# Conectores.net
KiCad netlist of a schematic drawn in Altium Designer
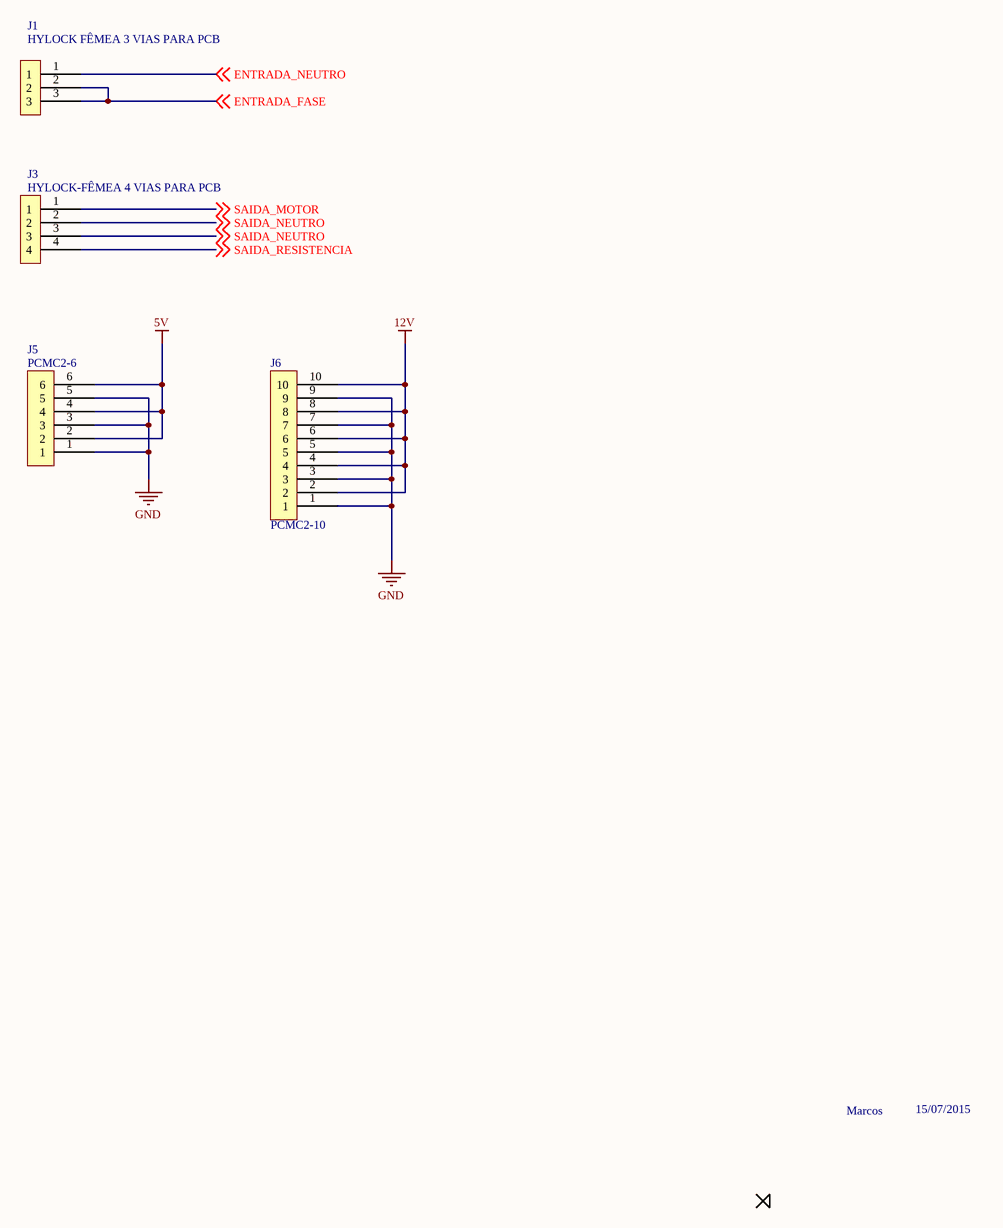
[diagram p0: Conectores.SchDoc]

(export (version "E")
  (design (tool "Eeschema 10.0.6"))
  (components
    (comp (ref "J1")
      (value "HYLOCK FÊMEA 3 VIAS PARA PCB")
      (footprint "CONECTOR HYLOCK 3 VIAS")
      (description "PCMC2-3")
      (libsource (lib "AquinoLib") (part "PCMC2-3"))
    )
    (comp (ref "J3")
      (value "HYLOCK-FÊMEA 4 VIAS PARA PCB")
      (footprint "CONECTOR HYLOK 4 VIAS")
      (description "PCMC2-4")
      (libsource (lib "AquinoLib") (part "PCMC2-4"))
    )
    (comp (ref "J5") (value "PCMC2-6") (footprint "PCMC2-6") (libsource (lib "AquinoLib") (part "PCMC2-6")))
    (comp (ref "J6")
      (value "PCMC2-10")
      (footprint "PCMC2-10")
      (libsource (lib "AquinoLib") (part "PCMC2-10"))
    )
  )
  (nets
    (net (code "1") (name "5V") (class "Default")
      (node (ref "J5") (pin "2") (pinfunction "2_2") (pintype "passive"))
      (node (ref "J5") (pin "4") (pinfunction "4_4") (pintype "passive"))
      (node (ref "J5") (pin "6") (pinfunction "6_6") (pintype "passive"))
    )
    (net (code "2") (name "12V") (class "Default")
      (node (ref "J6") (pin "10") (pinfunction "10_10") (pintype "passive"))
      (node (ref "J6") (pin "2") (pinfunction "2_2") (pintype "passive"))
      (node (ref "J6") (pin "4") (pinfunction "4_4") (pintype "passive"))
      (node (ref "J6") (pin "6") (pinfunction "6_6") (pintype "passive"))
      (node (ref "J6") (pin "8") (pinfunction "8_8") (pintype "passive"))
    )
    (net (code "3") (name "ENTRADA_FASE") (class "Default")
      (node (ref "J1") (pin "2") (pinfunction "2_2") (pintype "passive"))
      (node (ref "J1") (pin "3") (pinfunction "3_3") (pintype "passive"))
    )
    (net (code "4") (name "ENTRADA_NEUTRO") (class "Default")
      (node (ref "J1") (pin "1") (pinfunction "1_1") (pintype "passive"))
    )
    (net (code "5") (name "GND") (class "Default")
      (node (ref "J5") (pin "1") (pinfunction "1_1") (pintype "passive"))
      (node (ref "J5") (pin "3") (pinfunction "3_3") (pintype "passive"))
      (node (ref "J5") (pin "5") (pinfunction "5_5") (pintype "passive"))
      (node (ref "J6") (pin "1") (pinfunction "1_1") (pintype "passive"))
      (node (ref "J6") (pin "3") (pinfunction "3_3") (pintype "passive"))
      (node (ref "J6") (pin "5") (pinfunction "5_5") (pintype "passive"))
      (node (ref "J6") (pin "7") (pinfunction "7_7") (pintype "passive"))
      (node (ref "J6") (pin "9") (pinfunction "9_9") (pintype "passive"))
    )
    (net (code "6") (name "SAIDA_MOTOR") (class "Default")
      (node (ref "J3") (pin "1") (pinfunction "1_1") (pintype "passive"))
    )
    (net (code "7") (name "SAIDA_NEUTRO") (class "Default")
      (node (ref "J3") (pin "2") (pinfunction "2_2") (pintype "passive"))
      (node (ref "J3") (pin "3") (pinfunction "3_3") (pintype "passive"))
    )
    (net (code "8") (name "SAIDA_RESISTENCIA") (class "Default")
      (node (ref "J3") (pin "4") (pinfunction "4_4") (pintype "passive"))
    )
  )
)
